# NICLEO-XXXXRX.net
KiCad netlist of a schematic drawn in Altium Designer
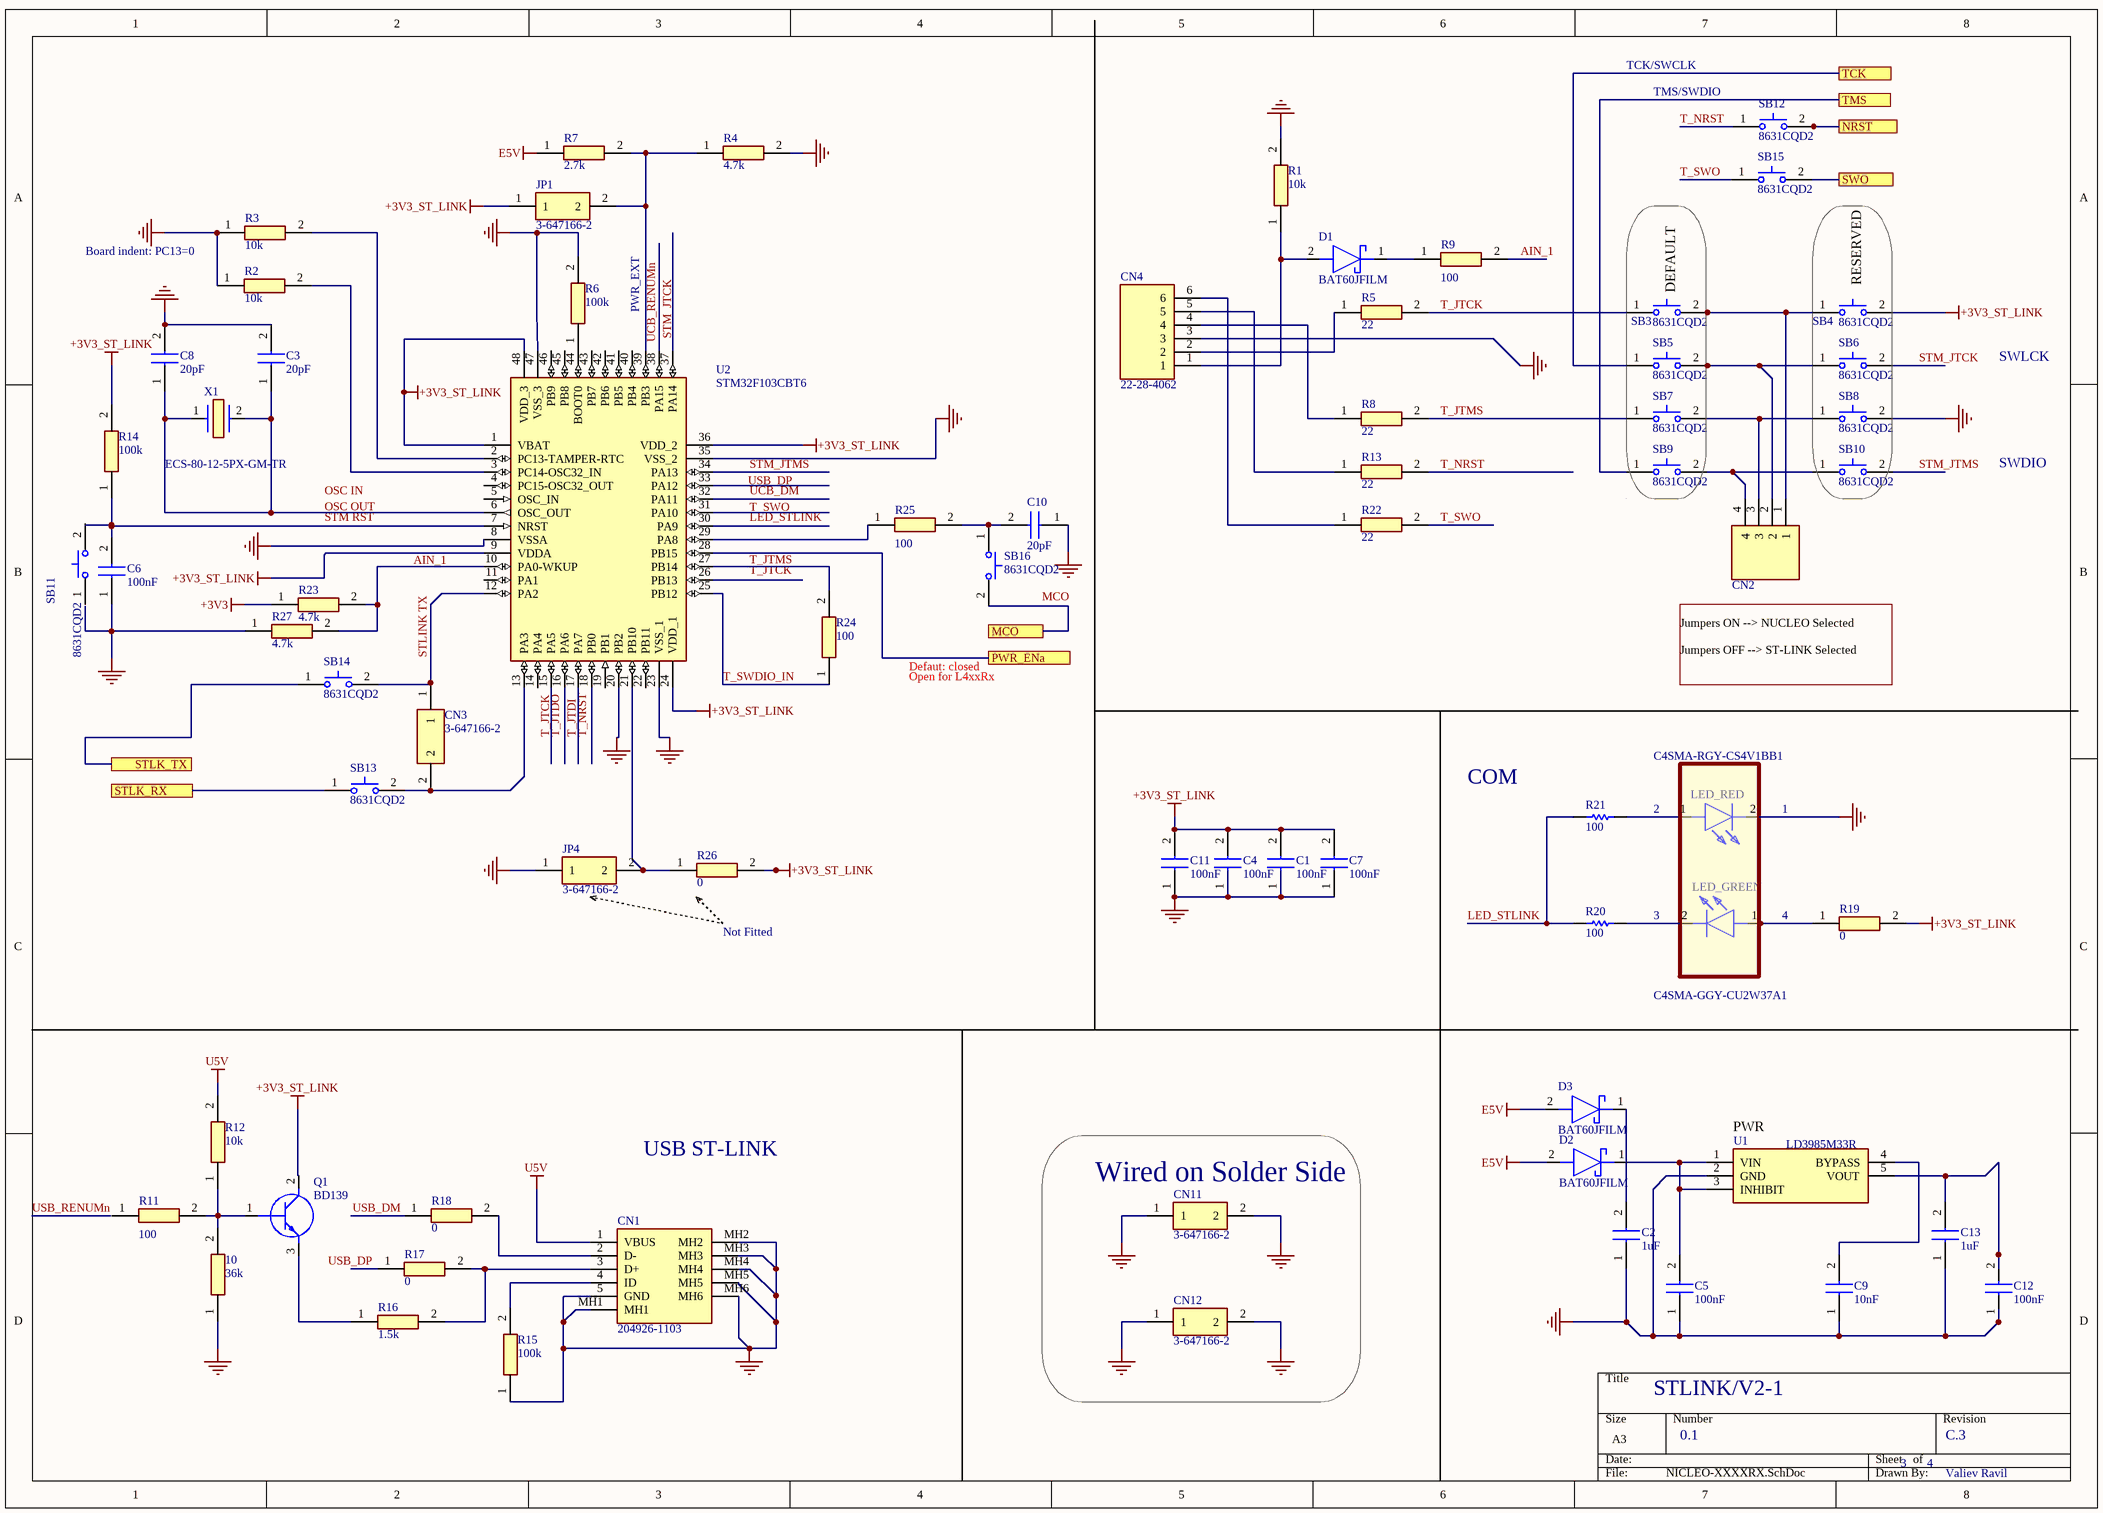
[diagram p0: NICLEO-XXXXRX.SchDoc]

(export (version "E")
  (design (tool "Eeschema 10.0.6"))
  (components
    (comp (ref "10")
      (value "36k")
      (footprint "SamacSys:RESC2012X55N")
      (description "Resistor")
      (fields (field (name "MANUFACTURER_PART_NUMBER") "TNPW080536K0BEEA"))
      (libsource (lib "*") (part "TNPW080536K0BEEA"))
    )
    (comp (ref "C1")
      (value "100nF")
      (footprint "SamacSys:CAPC1608X90N")
      (description "Capacitor")
      (fields
        (field (name "MANUFACTURER_PART_NUMBER") "06035C104K4T4A")
        (field (name "MOUSER PART NUMBER") "581-06035C104K4T4A")
      )
      (libsource (lib "*") (part "06035C104K4T4A"))
    )
    (comp (ref "C2")
      (value "1uF")
      (footprint "SamacSys:MAJx16")
      (description "Capacitor")
      (fields (field (name "MANUFACTURER_PART_NUMBER") "MAJCT168BB7105KTEA01"))
      (libsource (lib "*") (part "MAJCT168BB7105KTEA01"))
    )
    (comp (ref "C3")
      (value "20pF")
      (footprint "SamacSys:C1206")
      (description "Capacitor")
      (fields (field (name "MANUFACTURER_PART_NUMBER") "C1206C200KCGACTU"))
      (libsource (lib "*") (part "C1206C200KCGACTU"))
    )
    (comp (ref "C4")
      (value "100nF")
      (footprint "SamacSys:CAPC1608X90N")
      (description "Capacitor")
      (fields
        (field (name "MANUFACTURER_PART_NUMBER") "06035C104K4T4A")
        (field (name "MOUSER PART NUMBER") "581-06035C104K4T4A")
      )
      (libsource (lib "*") (part "06035C104K4T4A"))
    )
    (comp (ref "C5")
      (value "100nF")
      (footprint "SamacSys:CAPC1608X90N")
      (description "Capacitor")
      (fields
        (field (name "MANUFACTURER_PART_NUMBER") "06035C104K4T4A")
        (field (name "MOUSER PART NUMBER") "581-06035C104K4T4A")
      )
      (libsource (lib "*") (part "06035C104K4T4A"))
    )
    (comp (ref "C6")
      (value "100nF")
      (footprint "SamacSys:CAPC1608X90N")
      (description "Capacitor")
      (fields
        (field (name "MANUFACTURER_PART_NUMBER") "06035C104K4T4A")
        (field (name "MOUSER PART NUMBER") "581-06035C104K4T4A")
      )
      (libsource (lib "*") (part "06035C104K4T4A"))
    )
    (comp (ref "C7")
      (value "100nF")
      (footprint "SamacSys:CAPC1608X90N")
      (description "Capacitor")
      (fields
        (field (name "MANUFACTURER_PART_NUMBER") "06035C104K4T4A")
        (field (name "MOUSER PART NUMBER") "581-06035C104K4T4A")
      )
      (libsource (lib "*") (part "06035C104K4T4A"))
    )
    (comp (ref "C8")
      (value "20pF")
      (footprint "SamacSys:C1206")
      (description "Capacitor")
      (fields (field (name "MANUFACTURER_PART_NUMBER") "C1206C200KCGACTU"))
      (libsource (lib "*") (part "C1206C200KCGACTU"))
    )
    (comp (ref "C9")
      (value "10nF")
      (footprint "SamacSys:CAPC3316X145N")
      (description "Capacitor")
      (fields
        (field (name "MANUFACTURER_PART_NUMBER") "KGM31GCG2J103JU")
        (field (name "MOUSER PART NUMBER") "581-KGM31GCG2J103JU")
      )
      (libsource (lib "*") (part "KGM31GCG2J103JU"))
    )
    (comp (ref "C10")
      (value "20pF")
      (footprint "SamacSys:C1206")
      (description "Capacitor")
      (fields (field (name "MANUFACTURER_PART_NUMBER") "C1206C200KCGACTU"))
      (libsource (lib "*") (part "C1206C200KCGACTU"))
    )
    (comp (ref "C11")
      (value "100nF")
      (footprint "SamacSys:CAPC1608X90N")
      (description "Capacitor")
      (fields
        (field (name "MANUFACTURER_PART_NUMBER") "06035C104K4T4A")
        (field (name "MOUSER PART NUMBER") "581-06035C104K4T4A")
      )
      (libsource (lib "*") (part "06035C104K4T4A"))
    )
    (comp (ref "C12")
      (value "100nF")
      (footprint "SamacSys:CAPC1608X90N")
      (description "Capacitor")
      (fields
        (field (name "MANUFACTURER_PART_NUMBER") "06035C104K4T4A")
        (field (name "MOUSER PART NUMBER") "581-06035C104K4T4A")
      )
      (libsource (lib "*") (part "06035C104K4T4A"))
    )
    (comp (ref "C13")
      (value "1uF")
      (footprint "SamacSys:MAJx16")
      (description "Capacitor")
      (fields (field (name "MANUFACTURER_PART_NUMBER") "MAJCT168BB7105KTEA01"))
      (libsource (lib "*") (part "MAJCT168BB7105KTEA01"))
    )
    (comp (ref "CN1")
      (value "204926-1103")
      (footprint "SamacSys:2049261103")
      (description "Connector")
      (fields (field (name "MOUSER PART NUMBER") "538-204926-1103"))
      (libsource (lib "*") (part "204926-1103"))
    )
    (comp (ref "CN2")
      (value "53014-0410")
      (footprint "SamacSys:SHDR4W60P0X200_1X4_1200X435X1000P")
      (description "Connector")
      (fields (field (name "MOUSER PART NUMBER") "538-53014-0410"))
      (libsource (lib "*") (part "53014-0410"))
    )
    (comp (ref "CN3")
      (value "3-647166-2")
      (footprint "SamacSys:36471662")
      (description "Connector")
      (fields (field (name "MOUSER PART NUMBER") "571-3-647166-2"))
      (libsource (lib "") (part "3-647166-2_1"))
    )
    (comp (ref "CN4")
      (value "22-28-4062")
      (footprint "SamacSys:HDRV6W66P0X254_1X6_1524X249X838P")
      (description "Connector")
      (fields (field (name "MOUSER PART NUMBER") "538-22-28-4062"))
      (libsource (lib "*") (part "22-28-4062"))
    )
    (comp (ref "CN11")
      (value "3-647166-2")
      (footprint "SamacSys:36471662")
      (description "Connector")
      (fields (field (name "MOUSER PART NUMBER") "571-3-647166-2"))
      (libsource (lib "*") (part "3-647166-2"))
    )
    (comp (ref "CN12")
      (value "3-647166-2")
      (footprint "SamacSys:36471662")
      (description "Connector")
      (fields (field (name "MOUSER PART NUMBER") "571-3-647166-2"))
      (libsource (lib "*") (part "3-647166-2"))
    )
    (comp (ref "D1")
      (value "BAT60JFILM")
      (footprint "SamacSys:SOD2513X117N")
      (description "Schottky Diode")
      (fields (field (name "MOUSER PART NUMBER") "511-BAT60JFILM"))
      (libsource (lib "*") (part "BAT60JFILM"))
    )
    (comp (ref "D2")
      (value "BAT60JFILM")
      (footprint "SamacSys:SOD2513X117N")
      (description "Schottky Diode")
      (fields (field (name "MOUSER PART NUMBER") "511-BAT60JFILM"))
      (libsource (lib "*") (part "BAT60JFILM"))
    )
    (comp (ref "D3")
      (value "BAT60JFILM")
      (footprint "SamacSys:SOD2513X117N")
      (description "Schottky Diode")
      (fields (field (name "MOUSER PART NUMBER") "511-BAT60JFILM"))
      (libsource (lib "*") (part "BAT60JFILM"))
    )
    (comp (ref "JP1")
      (value "3-647166-2")
      (footprint "SamacSys:36471662")
      (description "Connector")
      (fields (field (name "MOUSER PART NUMBER") "571-3-647166-2"))
      (libsource (lib "*") (part "3-647166-2"))
    )
    (comp (ref "JP4")
      (value "3-647166-2")
      (footprint "SamacSys:36471662")
      (description "Connector")
      (fields (field (name "MOUSER PART NUMBER") "571-3-647166-2"))
      (libsource (lib "*") (part "3-647166-2"))
    )
    (comp (ref "LED_GREEN")
      (value "C4SMA-GGY-CU2W37A1")
      (footprint "SamacSys:C4SMAGGYCU2W37A1")
      (description "LED")
      (fields (field (name "MOUSER PART NUMBER") "941-C4SMAGGYCU2W37A1"))
      (libsource (lib "*") (part "C4SMA-GGY-CU2W37A1"))
    )
    (comp (ref "LED_RED")
      (value "C4SMA-RGY-CS4V1BB1")
      (footprint "SamacSys:C4SMARGYCS4V1BB1")
      (description "LED")
      (fields (field (name "MOUSER PART NUMBER") "941-C4SMARGYCS4V1BB1"))
      (libsource (lib "*") (part "C4SMA-RGY-CS4V1BB1"))
    )
    (comp (ref "Q1")
      (value "BD139")
      (footprint "SamacSys:TO254P290X760X1320-3P")
      (description "Transistor BJT NPN")
      (fields (field (name "MOUSER PART NUMBER") "511-BD139"))
      (libsource (lib "*") (part "BD139"))
    )
    (comp (ref "R1")
      (value "10k")
      (footprint "SamacSys:RESC3216X74N")
      (description "Resistor")
      (fields
        (field (name "MANUFACTURER_PART_NUMBER") "CRMV1206AF10K0FKE5")
        (field (name "MOUSER PART NUMBER") "71-RMV1206AF10K0FKE5")
      )
      (libsource (lib "*") (part "CRMV1206AF10K0FKE5"))
    )
    (comp (ref "R2")
      (value "10k")
      (footprint "SamacSys:RESC3216X74N")
      (description "Resistor")
      (fields
        (field (name "MANUFACTURER_PART_NUMBER") "CRMV1206AF10K0FKE5")
        (field (name "MOUSER PART NUMBER") "71-RMV1206AF10K0FKE5")
      )
      (libsource (lib "") (part "CRMV1206AF10K0FKE5_1"))
    )
    (comp (ref "R3")
      (value "10k")
      (footprint "SamacSys:RESC3216X74N")
      (description "Resistor")
      (fields
        (field (name "MANUFACTURER_PART_NUMBER") "CRMV1206AF10K0FKE5")
        (field (name "MOUSER PART NUMBER") "71-RMV1206AF10K0FKE5")
      )
      (libsource (lib "") (part "CRMV1206AF10K0FKE5_1"))
    )
    (comp (ref "R4")
      (value "4.7k")
      (footprint "SamacSys:RESC1005X37N")
      (description "Resistor")
      (fields
        (field (name "MANUFACTURER_PART_NUMBER") "MCS04020D4701BE000")
        (field (name "MOUSER PART NUMBER") "594-MCS04020D4701BE0")
      )
      (libsource (lib "*") (part "MCS04020D4701BE000"))
    )
    (comp (ref "R5")
      (value "22")
      (footprint "SamacSys:ERA6AEB1020V")
      (description "Resistor")
      (fields
        (field (name "MANUFACTURER_PART_NUMBER") "ERA-6AHD220V")
        (field (name "MOUSER PART NUMBER") "667-ERA-6AHD220V")
      )
      (libsource (lib "*") (part "ERA-6AHD220V"))
    )
    (comp (ref "R6")
      (value "100k")
      (footprint "SamacSys:RESC1005X40N")
      (description "Resistor")
      (fields
        (field (name "MANUFACTURER_PART_NUMBER") "SFR01MZPF1003")
        (field (name "MOUSER PART NUMBER") "755-SFR01MZPF1003")
      )
      (libsource (lib "*") (part "SFR01MZPF1003"))
    )
    (comp (ref "R7")
      (value "2.7k")
      (footprint "SamacSys:RESC3225X70N")
      (description "Resistor")
      (fields
        (field (name "MANUFACTURER_PART_NUMBER") "CRCW12102K70FKEAHP")
        (field (name "MOUSER PART NUMBER") "71-CRCW12102K70FKEAH")
      )
      (libsource (lib "*") (part "CRCW12102K70FKEAHP"))
    )
    (comp (ref "R8")
      (value "22")
      (footprint "SamacSys:ERA6AEB1020V")
      (description "Resistor")
      (fields
        (field (name "MANUFACTURER_PART_NUMBER") "ERA-6AHD220V")
        (field (name "MOUSER PART NUMBER") "667-ERA-6AHD220V")
      )
      (libsource (lib "*") (part "ERA-6AHD220V"))
    )
    (comp (ref "R9")
      (value "100")
      (footprint "SamacSys:ERA3AEB101V")
      (description "Resistor")
      (fields
        (field (name "MANUFACTURER_PART_NUMBER") "ERA-3AED101V")
        (field (name "MOUSER PART NUMBER") "667-ERA-3AED101V")
      )
      (libsource (lib "*") (part "ERA-3AED101V"))
    )
    (comp (ref "R11")
      (value "100")
      (footprint "SamacSys:ERA3AEB101V")
      (description "Resistor")
      (fields
        (field (name "MANUFACTURER_PART_NUMBER") "ERA-3AED101V")
        (field (name "MOUSER PART NUMBER") "667-ERA-3AED101V")
      )
      (libsource (lib "*") (part "ERA-3AED101V"))
    )
    (comp (ref "R12")
      (value "10k")
      (footprint "SamacSys:RESC3216X74N")
      (description "Resistor")
      (fields
        (field (name "MANUFACTURER_PART_NUMBER") "CRMV1206AF10K0FKE5")
        (field (name "MOUSER PART NUMBER") "71-RMV1206AF10K0FKE5")
      )
      (libsource (lib "*") (part "CRMV1206AF10K0FKE5"))
    )
    (comp (ref "R13")
      (value "22")
      (footprint "SamacSys:ERA6AEB1020V")
      (description "Resistor")
      (fields
        (field (name "MANUFACTURER_PART_NUMBER") "ERA-6AHD220V")
        (field (name "MOUSER PART NUMBER") "667-ERA-6AHD220V")
      )
      (libsource (lib "*") (part "ERA-6AHD220V"))
    )
    (comp (ref "R14")
      (value "100k")
      (footprint "SamacSys:RESC1005X40N")
      (description "Resistor")
      (fields
        (field (name "MANUFACTURER_PART_NUMBER") "SFR01MZPF1003")
        (field (name "MOUSER PART NUMBER") "755-SFR01MZPF1003")
      )
      (libsource (lib "*") (part "SFR01MZPF1003"))
    )
    (comp (ref "R15")
      (value "100k")
      (footprint "SamacSys:RESC1005X40N")
      (description "Resistor")
      (fields
        (field (name "MANUFACTURER_PART_NUMBER") "SFR01MZPF1003")
        (field (name "MOUSER PART NUMBER") "755-SFR01MZPF1003")
      )
      (libsource (lib "*") (part "SFR01MZPF1003"))
    )
    (comp (ref "R16")
      (value "1.5k")
      (footprint "SamacSys:RESC3116X65N")
      (description "Resistor")
      (fields
        (field (name "MANUFACTURER_PART_NUMBER") "CRCW12061K50FKEAHP")
        (field (name "MOUSER PART NUMBER") "71-CRCW12061K50FKEAH")
      )
      (libsource (lib "*") (part "CRCW12061K50FKEAHP"))
    )
    (comp (ref "R17")
      (value "0")
      (footprint "SamacSys:RESC2013X84N")
      (description "Resistor")
      (fields
        (field (name "MANUFACTURER_PART_NUMBER") "WSL080500000ZEA9")
        (field (name "MOUSER PART NUMBER") "71-WSL080500000ZEA9")
      )
      (libsource (lib "*") (part "WSL080500000ZEA9"))
    )
    (comp (ref "R18")
      (value "0")
      (footprint "SamacSys:RESC2013X84N")
      (description "Resistor")
      (fields
        (field (name "MANUFACTURER_PART_NUMBER") "WSL080500000ZEA9")
        (field (name "MOUSER PART NUMBER") "71-WSL080500000ZEA9")
      )
      (libsource (lib "*") (part "WSL080500000ZEA9"))
    )
    (comp (ref "R19")
      (value "0")
      (footprint "SamacSys:RESC2013X84N")
      (description "Resistor")
      (fields
        (field (name "MANUFACTURER_PART_NUMBER") "WSL080500000ZEA9")
        (field (name "MOUSER PART NUMBER") "71-WSL080500000ZEA9")
      )
      (libsource (lib "*") (part "WSL080500000ZEA9"))
    )
    (comp (ref "R20")
      (value "100")
      (description "Resistor")
      (libsource (lib "Simulation Generic Components") (part "Resistor"))
    )
    (comp (ref "R21")
      (value "100")
      (description "Resistor")
      (libsource (lib "Simulation Generic Components") (part "Resistor"))
    )
    (comp (ref "R22")
      (value "22")
      (footprint "SamacSys:ERA6AEB1020V")
      (description "Resistor")
      (fields
        (field (name "MANUFACTURER_PART_NUMBER") "ERA-6AHD220V")
        (field (name "MOUSER PART NUMBER") "667-ERA-6AHD220V")
      )
      (libsource (lib "*") (part "ERA-6AHD220V"))
    )
    (comp (ref "R23")
      (value "4.7k")
      (footprint "SamacSys:RESC1005X37N")
      (description "Resistor")
      (fields
        (field (name "MANUFACTURER_PART_NUMBER") "MCS04020D4701BE000")
        (field (name "MOUSER PART NUMBER") "594-MCS04020D4701BE0")
      )
      (libsource (lib "*") (part "MCS04020D4701BE000"))
    )
    (comp (ref "R24")
      (value "100")
      (footprint "SamacSys:ERA3AEB101V")
      (description "Resistor")
      (fields
        (field (name "MANUFACTURER_PART_NUMBER") "ERA-3AED101V")
        (field (name "MOUSER PART NUMBER") "667-ERA-3AED101V")
      )
      (libsource (lib "") (part "ERA-3AED101V_1"))
    )
    (comp (ref "R25")
      (value "100")
      (footprint "SamacSys:ERA3AEB101V")
      (description "Resistor")
      (fields
        (field (name "MANUFACTURER_PART_NUMBER") "ERA-3AED101V")
        (field (name "MOUSER PART NUMBER") "667-ERA-3AED101V")
      )
      (libsource (lib "*") (part "ERA-3AED101V"))
    )
    (comp (ref "R26")
      (value "0")
      (footprint "SamacSys:RESC2013X84N")
      (description "Resistor")
      (fields
        (field (name "MANUFACTURER_PART_NUMBER") "WSL080500000ZEA9")
        (field (name "MOUSER PART NUMBER") "71-WSL080500000ZEA9")
      )
      (libsource (lib "*") (part "WSL080500000ZEA9"))
    )
    (comp (ref "R27")
      (value "4.7k")
      (footprint "SamacSys:RESC1005X37N")
      (description "Resistor")
      (fields
        (field (name "MANUFACTURER_PART_NUMBER") "MCS04020D4701BE000")
        (field (name "MOUSER PART NUMBER") "594-MCS04020D4701BE0")
      )
      (libsource (lib "*") (part "MCS04020D4701BE000"))
    )
    (comp (ref "SB3")
      (value "8631CQD2")
      (footprint "SamacSys:8631CQD2")
      (description "Switch (2-Pin Push)")
      (fields (field (name "MOUSER PART NUMBER") "611-8631-261"))
      (libsource (lib "*") (part "8631CQD2"))
    )
    (comp (ref "SB4")
      (value "8631CQD2")
      (footprint "SamacSys:8631CQD2")
      (description "Switch (2-Pin Push)")
      (fields (field (name "MOUSER PART NUMBER") "611-8631-261"))
      (libsource (lib "*") (part "8631CQD2"))
    )
    (comp (ref "SB5")
      (value "8631CQD2")
      (footprint "SamacSys:8631CQD2")
      (description "Switch (2-Pin Push)")
      (fields (field (name "MOUSER PART NUMBER") "611-8631-261"))
      (libsource (lib "*") (part "8631CQD2"))
    )
    (comp (ref "SB6")
      (value "8631CQD2")
      (footprint "SamacSys:8631CQD2")
      (description "Switch (2-Pin Push)")
      (fields (field (name "MOUSER PART NUMBER") "611-8631-261"))
      (libsource (lib "*") (part "8631CQD2"))
    )
    (comp (ref "SB7")
      (value "8631CQD2")
      (footprint "SamacSys:8631CQD2")
      (description "Switch (2-Pin Push)")
      (fields (field (name "MOUSER PART NUMBER") "611-8631-261"))
      (libsource (lib "*") (part "8631CQD2"))
    )
    (comp (ref "SB8")
      (value "8631CQD2")
      (footprint "SamacSys:8631CQD2")
      (description "Switch (2-Pin Push)")
      (fields (field (name "MOUSER PART NUMBER") "611-8631-261"))
      (libsource (lib "*") (part "8631CQD2"))
    )
    (comp (ref "SB9")
      (value "8631CQD2")
      (footprint "SamacSys:8631CQD2")
      (description "Switch (2-Pin Push)")
      (fields (field (name "MOUSER PART NUMBER") "611-8631-261"))
      (libsource (lib "*") (part "8631CQD2"))
    )
    (comp (ref "SB10")
      (value "8631CQD2")
      (footprint "SamacSys:8631CQD2")
      (description "Switch (2-Pin Push)")
      (fields (field (name "MOUSER PART NUMBER") "611-8631-261"))
      (libsource (lib "*") (part "8631CQD2"))
    )
    (comp (ref "SB11")
      (value "8631CQD2")
      (footprint "SamacSys:8631CQD2")
      (description "Switch (2-Pin Push)")
      (fields (field (name "MOUSER PART NUMBER") "611-8631-261"))
      (libsource (lib "*") (part "8631CQD2"))
    )
    (comp (ref "SB12")
      (value "8631CQD2")
      (footprint "SamacSys:8631CQD2")
      (description "Switch (2-Pin Push)")
      (fields (field (name "MOUSER PART NUMBER") "611-8631-261"))
      (libsource (lib "*") (part "8631CQD2"))
    )
    (comp (ref "SB13")
      (value "8631CQD2")
      (footprint "SamacSys:8631CQD2")
      (description "Switch (2-Pin Push)")
      (fields (field (name "MOUSER PART NUMBER") "611-8631-261"))
      (libsource (lib "*") (part "8631CQD2"))
    )
    (comp (ref "SB14")
      (value "8631CQD2")
      (footprint "SamacSys:8631CQD2")
      (description "Switch (2-Pin Push)")
      (fields (field (name "MOUSER PART NUMBER") "611-8631-261"))
      (libsource (lib "*") (part "8631CQD2"))
    )
    (comp (ref "SB15")
      (value "8631CQD2")
      (footprint "SamacSys:8631CQD2")
      (description "Switch (2-Pin Push)")
      (fields (field (name "MOUSER PART NUMBER") "611-8631-261"))
      (libsource (lib "*") (part "8631CQD2"))
    )
    (comp (ref "SB16")
      (value "8631CQD2")
      (footprint "SamacSys:8631CQD2")
      (description "Switch (2-Pin Push)")
      (fields (field (name "MOUSER PART NUMBER") "611-8631-261"))
      (libsource (lib "*") (part "8631CQD2"))
    )
    (comp (ref "U1")
      (value "LD3985M33R")
      (footprint "SamacSys:SOT95P280X145-5N")
      (description "Integrated Circuit")
      (fields (field (name "MOUSER PART NUMBER") "511-LD3985M33R"))
      (libsource (lib "*") (part "LD3985M33R"))
    )
    (comp (ref "U2")
      (value "STM32F103CBT6")
      (footprint "SamacSys:QFP50P900X900X160-48N")
      (description "Integrated Circuit")
      (fields (field (name "MOUSER PART NUMBER") "511-STM32F103CBT6"))
      (libsource (lib "*") (part "STM32F103CBT6"))
    )
    (comp (ref "X1")
      (value "ECS-80-12-5PX-GM-TR")
      (footprint "SamacSys:ECS80125PXGMTR")
      (description "Crystal or Oscillator")
      (fields (field (name "MOUSER PART NUMBER") "520-80-12-5PX-GM-TR"))
      (libsource (lib "*") (part "ECS-80-12-5PX-GM-TR"))
    )
  )
  (nets
    (net (code "1") (name "+3V3") (class "Default")
      (node (ref "R23") (pin "1") (pinfunction "1_1") (pintype "passive"))
    )
    (net (code "2") (name "+3V3_ST_LINK") (class "Default")
      (node (ref "C1") (pin "2") (pinfunction "2_2") (pintype "passive"))
      (node (ref "C11") (pin "2") (pinfunction "2_2") (pintype "passive"))
      (node (ref "C4") (pin "2") (pinfunction "2_2") (pintype "passive"))
      (node (ref "C7") (pin "2") (pinfunction "2_2") (pintype "passive"))
      (node (ref "JP1") (pin "1") (pinfunction "1_1") (pintype "passive"))
      (node (ref "Q1") (pin "2") (pinfunction "C_2") (pintype "passive"))
      (node (ref "R14") (pin "2") (pinfunction "2_2") (pintype "passive"))
      (node (ref "R19") (pin "2") (pinfunction "2_2") (pintype "passive"))
      (node (ref "R26") (pin "2") (pinfunction "2_2") (pintype "passive"))
      (node (ref "SB4") (pin "2") (pinfunction "N.O._2_2") (pintype "passive"))
      (node (ref "U2") (pin "1") (pinfunction "VBAT_1") (pintype "passive"))
      (node (ref "U2") (pin "24") (pinfunction "VDD_1_24") (pintype "passive"))
      (node (ref "U2") (pin "36") (pinfunction "VDD_2_36") (pintype "passive"))
      (node (ref "U2") (pin "48") (pinfunction "VDD_3_48") (pintype "passive"))
      (node (ref "U2") (pin "9") (pinfunction "VDDA_9") (pintype "passive"))
    )
    (net (code "3") (name "/MCO") (class "Default")
      (node (ref "SB16") (pin "2") (pinfunction "N.O._2_2") (pintype "passive"))
    )
    (net (code "4") (name "/NRST") (class "Default")
      (node (ref "SB12") (pin "2") (pinfunction "N.O._2_2") (pintype "passive"))
    )
    (net (code "5") (name "/PWR_ENa") (class "Default")
      (node (ref "U2") (pin "28") (pinfunction "PB15_28") (pintype "bidirectional"))
    )
    (net (code "6") (name "/STLK_RX") (class "Default")
      (node (ref "SB13") (pin "1") (pinfunction "N.O._1_1") (pintype "passive"))
    )
    (net (code "7") (name "/STLK_TX") (class "Default")
      (node (ref "SB14") (pin "1") (pinfunction "N.O._1_1") (pintype "passive"))
    )
    (net (code "8") (name "/SWO") (class "Default")
      (node (ref "SB15") (pin "2") (pinfunction "N.O._2_2") (pintype "passive"))
    )
    (net (code "9") (name "/TCK") (class "Default")
      (node (ref "SB5") (pin "1") (pinfunction "N.O._1_1") (pintype "passive"))
    )
    (net (code "10") (name "/TMS") (class "Default")
      (node (ref "SB9") (pin "1") (pinfunction "N.O._1_1") (pintype "passive"))
    )
    (net (code "11") (name "E5V") (class "Default")
      (node (ref "D2") (pin "2") (pinfunction "A_2") (pintype "passive"))
      (node (ref "D3") (pin "2") (pinfunction "A_2") (pintype "passive"))
      (node (ref "R7") (pin "1") (pinfunction "1_1") (pintype "passive"))
    )
    (net (code "12") (name "GND") (class "Default")
      (node (ref "10") (pin "1") (pinfunction "1_1") (pintype "passive"))
      (node (ref "C1") (pin "1") (pinfunction "1_1") (pintype "passive"))
      (node (ref "C10") (pin "1") (pinfunction "1_1") (pintype "passive"))
      (node (ref "C11") (pin "1") (pinfunction "1_1") (pintype "passive"))
      (node (ref "C12") (pin "1") (pinfunction "1_1") (pintype "passive"))
      (node (ref "C13") (pin "1") (pinfunction "1_1") (pintype "passive"))
      (node (ref "C2") (pin "1") (pinfunction "1_1") (pintype "passive"))
      (node (ref "C3") (pin "2") (pinfunction "2_2") (pintype "passive"))
      (node (ref "C4") (pin "1") (pinfunction "1_1") (pintype "passive"))
      (node (ref "C5") (pin "1") (pinfunction "1_1") (pintype "passive"))
      (node (ref "C6") (pin "1") (pinfunction "1_1") (pintype "passive"))
      (node (ref "C7") (pin "1") (pinfunction "1_1") (pintype "passive"))
      (node (ref "C8") (pin "2") (pinfunction "2_2") (pintype "passive"))
      (node (ref "C9") (pin "1") (pinfunction "1_1") (pintype "passive"))
      (node (ref "CN1") (pin "5") (pinfunction "GND_5") (pintype "passive"))
      (node (ref "CN1") (pin "MH1") (pinfunction "MH1_MH1") (pintype "passive"))
      (node (ref "CN1") (pin "MH2") (pinfunction "MH2_MH2") (pintype "passive"))
      (node (ref "CN1") (pin "MH3") (pinfunction "MH3_MH3") (pintype "passive"))
      (node (ref "CN1") (pin "MH4") (pinfunction "MH4_MH4") (pintype "passive"))
      (node (ref "CN1") (pin "MH5") (pinfunction "MH5_MH5") (pintype "passive"))
      (node (ref "CN1") (pin "MH6") (pinfunction "MH6_MH6") (pintype "passive"))
      (node (ref "CN11") (pin "1") (pinfunction "1_1") (pintype "passive"))
      (node (ref "CN11") (pin "2") (pinfunction "2_2") (pintype "passive"))
      (node (ref "CN12") (pin "1") (pinfunction "1_1") (pintype "passive"))
      (node (ref "CN12") (pin "2") (pinfunction "2_2") (pintype "passive"))
      (node (ref "CN4") (pin "3") (pinfunction "3_3") (pintype "passive"))
      (node (ref "JP4") (pin "1") (pinfunction "1_1") (pintype "passive"))
      (node (ref "LED_RED") (pin "2") (pinfunction "K_2") (pintype "passive"))
      (node (ref "R1") (pin "2") (pinfunction "2_2") (pintype "passive"))
      (node (ref "R15") (pin "1") (pinfunction "1_1") (pintype "passive"))
      (node (ref "R2") (pin "1") (pinfunction "1_1") (pintype "passive"))
      (node (ref "R27") (pin "1") (pinfunction "1_1") (pintype "passive"))
      (node (ref "R3") (pin "1") (pinfunction "1_1") (pintype "passive"))
      (node (ref "R4") (pin "2") (pinfunction "2_2") (pintype "passive"))
      (node (ref "R6") (pin "2") (pinfunction "2_2") (pintype "passive"))
      (node (ref "SB8") (pin "2") (pinfunction "N.O._2_2") (pintype "passive"))
      (node (ref "U1") (pin "2") (pinfunction "GND_2") (pintype "passive"))
      (node (ref "U2") (pin "20") (pinfunction "PB2_20") (pintype "bidirectional"))
      (node (ref "U2") (pin "23") (pinfunction "VSS_1_23") (pintype "passive"))
      (node (ref "U2") (pin "35") (pinfunction "VSS_2_35") (pintype "passive"))
      (node (ref "U2") (pin "47") (pinfunction "VSS_3_47") (pintype "passive"))
      (node (ref "U2") (pin "8") (pinfunction "VSSA_8") (pintype "passive"))
    )
    (net (code "13") (name "Net-(CN1-D+)") (class "Default")
      (node (ref "CN1") (pin "3") (pinfunction "D+_3") (pintype "passive"))
      (node (ref "R16") (pin "2") (pinfunction "2_2") (pintype "passive"))
      (node (ref "R17") (pin "2") (pinfunction "2_2") (pintype "passive"))
    )
    (net (code "14") (name "Net-(CN1-D-)") (class "Default")
      (node (ref "CN1") (pin "2") (pinfunction "D-_2") (pintype "passive"))
      (node (ref "R18") (pin "2") (pinfunction "2_2") (pintype "passive"))
    )
    (net (code "15") (name "Net-(CN1-ID)") (class "Default")
      (node (ref "CN1") (pin "4") (pinfunction "ID_4") (pintype "passive"))
      (node (ref "R15") (pin "2") (pinfunction "2_2") (pintype "passive"))
    )
    (net (code "16") (name "Net-(CN4-Pad2)") (class "Default")
      (node (ref "CN4") (pin "2") (pinfunction "2_2") (pintype "passive"))
      (node (ref "R5") (pin "1") (pinfunction "1_1") (pintype "passive"))
    )
    (net (code "17") (name "Net-(CN4-Pad4)") (class "Default")
      (node (ref "CN4") (pin "4") (pinfunction "4_4") (pintype "passive"))
      (node (ref "R8") (pin "1") (pinfunction "1_1") (pintype "passive"))
    )
    (net (code "18") (name "Net-(CN4-Pad5)") (class "Default")
      (node (ref "CN4") (pin "5") (pinfunction "5_5") (pintype "passive"))
      (node (ref "R13") (pin "1") (pinfunction "1_1") (pintype "passive"))
    )
    (net (code "19") (name "Net-(CN4-Pad6)") (class "Default")
      (node (ref "CN4") (pin "6") (pinfunction "6_6") (pintype "passive"))
      (node (ref "R22") (pin "1") (pinfunction "1_1") (pintype "passive"))
    )
    (net (code "20") (name "Net-(D1-A)") (class "Default")
      (node (ref "CN4") (pin "1") (pinfunction "1_1") (pintype "passive"))
      (node (ref "D1") (pin "2") (pinfunction "A_2") (pintype "passive"))
      (node (ref "R1") (pin "1") (pinfunction "1_1") (pintype "passive"))
    )
    (net (code "21") (name "Net-(D1-K)") (class "Default")
      (node (ref "D1") (pin "1") (pinfunction "K_1") (pintype "passive"))
      (node (ref "R9") (pin "1") (pinfunction "1_1") (pintype "passive"))
    )
    (net (code "22") (name "Net-(D2-K)") (class "Default")
      (node (ref "C5") (pin "2") (pinfunction "2_2") (pintype "passive"))
      (node (ref "D2") (pin "1") (pinfunction "K_1") (pintype "passive"))
      (node (ref "U1") (pin "1") (pinfunction "VIN_1") (pintype "passive"))
      (node (ref "U1") (pin "3") (pinfunction "INHIBIT_3") (pintype "passive"))
    )
    (net (code "23") (name "Net-(D3-K)") (class "Default")
      (node (ref "C2") (pin "2") (pinfunction "2_2") (pintype "passive"))
      (node (ref "D3") (pin "1") (pinfunction "K_1") (pintype "passive"))
    )
    (net (code "24") (name "Net-(LED_GREEN-A)") (class "Default")
      (node (ref "LED_GREEN") (pin "1") (pinfunction "A_1") (pintype "passive"))
      (node (ref "R19") (pin "1") (pinfunction "1_1") (pintype "passive"))
    )
    (net (code "25") (name "Net-(LED_GREEN-K)") (class "Default")
      (node (ref "LED_GREEN") (pin "2") (pinfunction "K_2") (pintype "passive"))
      (node (ref "R20") (pin "2") (pinfunction "2_2") (pintype "passive"))
    )
    (net (code "26") (name "Net-(LED_RED-A)") (class "Default")
      (node (ref "LED_RED") (pin "1") (pinfunction "A_1") (pintype "passive"))
      (node (ref "R21") (pin "2") (pinfunction "2_2") (pintype "passive"))
    )
    (net (code "27") (name "Net-(Q1-B)") (class "Default")
      (node (ref "10") (pin "2") (pinfunction "2_2") (pintype "passive"))
      (node (ref "Q1") (pin "1") (pinfunction "B_1") (pintype "passive"))
      (node (ref "R11") (pin "2") (pinfunction "2_2") (pintype "passive"))
      (node (ref "R12") (pin "1") (pinfunction "1_1") (pintype "passive"))
    )
    (net (code "28") (name "Net-(Q1-E)") (class "Default")
      (node (ref "Q1") (pin "3") (pinfunction "E_3") (pintype "passive"))
      (node (ref "R16") (pin "1") (pinfunction "1_1") (pintype "passive"))
    )
    (net (code "29") (name "Net-(R20-Pad1)") (class "Default")
      (node (ref "R20") (pin "1") (pinfunction "1_1") (pintype "passive"))
      (node (ref "R21") (pin "1") (pinfunction "1_1") (pintype "passive"))
    )
    (net (code "30") (name "Net-(SB3-N.O._1)") (class "Default")
      (node (ref "R5") (pin "2") (pinfunction "2_2") (pintype "passive"))
      (node (ref "SB3") (pin "1") (pinfunction "N.O._1_1") (pintype "passive"))
    )
    (net (code "31") (name "Net-(SB3-N.O._2)") (class "Default")
      (node (ref "CN2") (pin "1") (pinfunction "1_1") (pintype "passive"))
      (node (ref "SB3") (pin "2") (pinfunction "N.O._2_2") (pintype "passive"))
      (node (ref "SB4") (pin "1") (pinfunction "N.O._1_1") (pintype "passive"))
    )
    (net (code "32") (name "Net-(SB5-N.O._2)") (class "Default")
      (node (ref "CN2") (pin "2") (pinfunction "2_2") (pintype "passive"))
      (node (ref "SB5") (pin "2") (pinfunction "N.O._2_2") (pintype "passive"))
      (node (ref "SB6") (pin "1") (pinfunction "N.O._1_1") (pintype "passive"))
    )
    (net (code "33") (name "Net-(SB7-N.O._1)") (class "Default")
      (node (ref "R8") (pin "2") (pinfunction "2_2") (pintype "passive"))
      (node (ref "SB7") (pin "1") (pinfunction "N.O._1_1") (pintype "passive"))
    )
    (net (code "34") (name "Net-(SB7-N.O._2)") (class "Default")
      (node (ref "CN2") (pin "3") (pinfunction "3_3") (pintype "passive"))
      (node (ref "SB7") (pin "2") (pinfunction "N.O._2_2") (pintype "passive"))
      (node (ref "SB8") (pin "1") (pinfunction "N.O._1_1") (pintype "passive"))
    )
    (net (code "35") (name "Net-(SB10-N.O._1)") (class "Default")
      (node (ref "CN2") (pin "4") (pinfunction "4_4") (pintype "passive"))
      (node (ref "SB10") (pin "1") (pinfunction "N.O._1_1") (pintype "passive"))
      (node (ref "SB9") (pin "2") (pinfunction "N.O._2_2") (pintype "passive"))
    )
    (net (code "36") (name "Net-(SB13-N.O._2)") (class "Default")
      (node (ref "CN3") (pin "2") (pinfunction "2_2") (pintype "passive"))
      (node (ref "SB13") (pin "2") (pinfunction "N.O._2_2") (pintype "passive"))
      (node (ref "U2") (pin "13") (pinfunction "PA3_13") (pintype "bidirectional"))
    )
    (net (code "37") (name "Net-(SB14-N.O._2)") (class "Default")
      (node (ref "CN3") (pin "1") (pinfunction "1_1") (pintype "passive"))
      (node (ref "SB14") (pin "2") (pinfunction "N.O._2_2") (pintype "passive"))
      (node (ref "U2") (pin "12") (pinfunction "PA2_12") (pintype "bidirectional"))
    )
    (net (code "38") (name "Net-(SB16-N.O._1)") (class "Default")
      (node (ref "C10") (pin "2") (pinfunction "2_2") (pintype "passive"))
      (node (ref "R25") (pin "2") (pinfunction "2_2") (pintype "passive"))
      (node (ref "SB16") (pin "1") (pinfunction "N.O._1_1") (pintype "passive"))
    )
    (net (code "39") (name "Net-(U1-BYPASS)") (class "Default")
      (node (ref "C9") (pin "2") (pinfunction "2_2") (pintype "passive"))
      (node (ref "U1") (pin "4") (pinfunction "BYPASS_4") (pintype "passive"))
    )
    (net (code "40") (name "Net-(U1-VOUT)") (class "Default")
      (node (ref "C12") (pin "2") (pinfunction "2_2") (pintype "passive"))
      (node (ref "C13") (pin "2") (pinfunction "2_2") (pintype "passive"))
      (node (ref "U1") (pin "5") (pinfunction "VOUT_5") (pintype "passive"))
    )
    (net (code "41") (name "Net-(U2-BOOT0)") (class "Default")
      (node (ref "R6") (pin "1") (pinfunction "1_1") (pintype "passive"))
      (node (ref "U2") (pin "44") (pinfunction "BOOT0_44") (pintype "bidirectional"))
    )
    (net (code "42") (name "Net-(U2-NRST)") (class "Default")
      (node (ref "C6") (pin "2") (pinfunction "2_2") (pintype "passive"))
      (node (ref "R14") (pin "1") (pinfunction "1_1") (pintype "passive"))
      (node (ref "U2") (pin "7") (pinfunction "NRST_7") (pintype "input"))
    )
    (net (code "43") (name "Net-(U2-OSC_OUT)") (class "Default")
      (node (ref "C3") (pin "1") (pinfunction "1_1") (pintype "passive"))
      (node (ref "C8") (pin "1") (pinfunction "1_1") (pintype "passive"))
      (node (ref "U2") (pin "6") (pinfunction "OSC_OUT_6") (pintype "output"))
      (node (ref "X1") (pin "1") (pinfunction "1_1") (pintype "passive"))
      (node (ref "X1") (pin "2") (pinfunction "2_2") (pintype "passive"))
    )
    (net (code "44") (name "Net-(U2-PA0-WKUP)") (class "Default")
      (node (ref "R23") (pin "2") (pinfunction "2_2") (pintype "passive"))
      (node (ref "R27") (pin "2") (pinfunction "2_2") (pintype "passive"))
      (node (ref "U2") (pin "10") (pinfunction "PA0-WKUP_10") (pintype "bidirectional"))
    )
    (net (code "45") (name "Net-(U2-PA8)") (class "Default")
      (node (ref "R25") (pin "1") (pinfunction "1_1") (pintype "passive"))
      (node (ref "U2") (pin "29") (pinfunction "PA8_29") (pintype "bidirectional"))
    )
    (net (code "46") (name "Net-(U2-PB3)") (class "Default")
      (node (ref "JP1") (pin "2") (pinfunction "2_2") (pintype "passive"))
      (node (ref "R4") (pin "1") (pinfunction "1_1") (pintype "passive"))
      (node (ref "R7") (pin "2") (pinfunction "2_2") (pintype "passive"))
      (node (ref "U2") (pin "39") (pinfunction "PB3_39") (pintype "bidirectional"))
    )
    (net (code "47") (name "Net-(U2-PB10)") (class "Default")
      (node (ref "JP4") (pin "2") (pinfunction "2_2") (pintype "passive"))
      (node (ref "R26") (pin "1") (pinfunction "1_1") (pintype "passive"))
      (node (ref "U2") (pin "21") (pinfunction "PB10_21") (pintype "bidirectional"))
    )
    (net (code "48") (name "Net-(U2-PB12)") (class "Default")
      (node (ref "R24") (pin "1") (pinfunction "1_1") (pintype "passive"))
      (node (ref "U2") (pin "25") (pinfunction "PB12_25") (pintype "bidirectional"))
    )
    (net (code "49") (name "Net-(U2-PB14)") (class "Default")
      (node (ref "R24") (pin "2") (pinfunction "2_2") (pintype "passive"))
      (node (ref "U2") (pin "27") (pinfunction "PB14_27") (pintype "bidirectional"))
    )
    (net (code "50") (name "Net-(U2-PC13-TAMPER-RTC)") (class "Default")
      (node (ref "R3") (pin "2") (pinfunction "2_2") (pintype "passive"))
      (node (ref "U2") (pin "2") (pinfunction "PC13-TAMPER-RTC_2") (pintype "bidirectional"))
    )
    (net (code "51") (name "Net-(U2-PC14-OSC32_IN)") (class "Default")
      (node (ref "R2") (pin "2") (pinfunction "2_2") (pintype "passive"))
      (node (ref "U2") (pin "3") (pinfunction "PC14-OSC32_IN_3") (pintype "bidirectional"))
    )
    (net (code "52") (name "U5V") (class "Default")
      (node (ref "CN1") (pin "1") (pinfunction "VBUS_1") (pintype "passive"))
      (node (ref "R12") (pin "2") (pinfunction "2_2") (pintype "passive"))
    )
    (net (code "53") (name "unconnected-(R9-Pad2)") (class "Default")
      (node (ref "R9") (pin "2") (pinfunction "2_2") (pintype "passive"))
    )
    (net (code "54") (name "unconnected-(R11-Pad1)") (class "Default")
      (node (ref "R11") (pin "1") (pinfunction "1_1") (pintype "passive"))
    )
    (net (code "55") (name "unconnected-(R13-Pad2)") (class "Default")
      (node (ref "R13") (pin "2") (pinfunction "2_2") (pintype "passive"))
    )
    (net (code "56") (name "unconnected-(R17-Pad1)") (class "Default")
      (node (ref "R17") (pin "1") (pinfunction "1_1") (pintype "passive"))
    )
    (net (code "57") (name "unconnected-(R18-Pad1)") (class "Default")
      (node (ref "R18") (pin "1") (pinfunction "1_1") (pintype "passive"))
    )
    (net (code "58") (name "unconnected-(R22-Pad2)") (class "Default")
      (node (ref "R22") (pin "2") (pinfunction "2_2") (pintype "passive"))
    )
    (net (code "59") (name "unconnected-(SB6-N.O._2-Pad2)") (class "Default")
      (node (ref "SB6") (pin "2") (pinfunction "N.O._2_2") (pintype "passive"))
    )
    (net (code "60") (name "unconnected-(SB10-N.O._2-Pad2)") (class "Default")
      (node (ref "SB10") (pin "2") (pinfunction "N.O._2_2") (pintype "passive"))
    )
    (net (code "61") (name "unconnected-(SB11-N.O._1-Pad1)") (class "Default")
      (node (ref "SB11") (pin "1") (pinfunction "N.O._1_1") (pintype "passive"))
    )
    (net (code "62") (name "unconnected-(SB11-N.O._2-Pad2)") (class "Default")
      (node (ref "SB11") (pin "2") (pinfunction "N.O._2_2") (pintype "passive"))
    )
    (net (code "63") (name "unconnected-(SB12-N.O._1-Pad1)") (class "Default")
      (node (ref "SB12") (pin "1") (pinfunction "N.O._1_1") (pintype "passive"))
    )
    (net (code "64") (name "unconnected-(SB15-N.O._1-Pad1)") (class "Default")
      (node (ref "SB15") (pin "1") (pinfunction "N.O._1_1") (pintype "passive"))
    )
    (net (code "65") (name "unconnected-(U2-OSC_IN-Pad5)") (class "Default")
      (node (ref "U2") (pin "5") (pinfunction "OSC_IN_5") (pintype "input"))
    )
    (net (code "66") (name "unconnected-(U2-PA1-Pad11)") (class "Default")
      (node (ref "U2") (pin "11") (pinfunction "PA1_11") (pintype "bidirectional"))
    )
    (net (code "67") (name "unconnected-(U2-PA4-Pad14)") (class "Default")
      (node (ref "U2") (pin "14") (pinfunction "PA4_14") (pintype "bidirectional"))
    )
    (net (code "68") (name "unconnected-(U2-PA5-Pad15)") (class "Default")
      (node (ref "U2") (pin "15") (pinfunction "PA5_15") (pintype "bidirectional"))
    )
    (net (code "69") (name "unconnected-(U2-PA6-Pad16)") (class "Default")
      (node (ref "U2") (pin "16") (pinfunction "PA6_16") (pintype "bidirectional"))
    )
    (net (code "70") (name "unconnected-(U2-PA7-Pad17)") (class "Default")
      (node (ref "U2") (pin "17") (pinfunction "PA7_17") (pintype "bidirectional"))
    )
    (net (code "71") (name "unconnected-(U2-PA9-Pad30)") (class "Default")
      (node (ref "U2") (pin "30") (pinfunction "PA9_30") (pintype "bidirectional"))
    )
    (net (code "72") (name "unconnected-(U2-PA10-Pad31)") (class "Default")
      (node (ref "U2") (pin "31") (pinfunction "PA10_31") (pintype "bidirectional"))
    )
    (net (code "73") (name "unconnected-(U2-PA11-Pad32)") (class "Default")
      (node (ref "U2") (pin "32") (pinfunction "PA11_32") (pintype "bidirectional"))
    )
    (net (code "74") (name "unconnected-(U2-PA12-Pad33)") (class "Default")
      (node (ref "U2") (pin "33") (pinfunction "PA12_33") (pintype "bidirectional"))
    )
    (net (code "75") (name "unconnected-(U2-PA13-Pad34)") (class "Default")
      (node (ref "U2") (pin "34") (pinfunction "PA13_34") (pintype "bidirectional"))
    )
    (net (code "76") (name "unconnected-(U2-PA14-Pad37)") (class "Default")
      (node (ref "U2") (pin "37") (pinfunction "PA14_37") (pintype "bidirectional"))
    )
    (net (code "77") (name "unconnected-(U2-PA15-Pad38)") (class "Default")
      (node (ref "U2") (pin "38") (pinfunction "PA15_38") (pintype "bidirectional"))
    )
    (net (code "78") (name "unconnected-(U2-PB0-Pad18)") (class "Default")
      (node (ref "U2") (pin "18") (pinfunction "PB0_18") (pintype "bidirectional"))
    )
    (net (code "79") (name "unconnected-(U2-PB1-Pad19)") (class "Default")
      (node (ref "U2") (pin "19") (pinfunction "PB1_19") (pintype "input"))
    )
    (net (code "80") (name "unconnected-(U2-PB4-Pad40)") (class "Default")
      (node (ref "U2") (pin "40") (pinfunction "PB4_40") (pintype "bidirectional"))
    )
    (net (code "81") (name "unconnected-(U2-PB5-Pad41)") (class "Default")
      (node (ref "U2") (pin "41") (pinfunction "PB5_41") (pintype "bidirectional"))
    )
    (net (code "82") (name "unconnected-(U2-PB6-Pad42)") (class "Default")
      (node (ref "U2") (pin "42") (pinfunction "PB6_42") (pintype "bidirectional"))
    )
    (net (code "83") (name "unconnected-(U2-PB7-Pad43)") (class "Default")
      (node (ref "U2") (pin "43") (pinfunction "PB7_43") (pintype "bidirectional"))
    )
    (net (code "84") (name "unconnected-(U2-PB8-Pad45)") (class "Default")
      (node (ref "U2") (pin "45") (pinfunction "PB8_45") (pintype "bidirectional"))
    )
    (net (code "85") (name "unconnected-(U2-PB9-Pad46)") (class "Default")
      (node (ref "U2") (pin "46") (pinfunction "PB9_46") (pintype "bidirectional"))
    )
    (net (code "86") (name "unconnected-(U2-PB11-Pad22)") (class "Default")
      (node (ref "U2") (pin "22") (pinfunction "PB11_22") (pintype "bidirectional"))
    )
    (net (code "87") (name "unconnected-(U2-PB13-Pad26)") (class "Default")
      (node (ref "U2") (pin "26") (pinfunction "PB13_26") (pintype "bidirectional"))
    )
    (net (code "88") (name "unconnected-(U2-PC15-OSC32_OUT-Pad4)") (class "Default")
      (node (ref "U2") (pin "4") (pinfunction "PC15-OSC32_OUT_4") (pintype "bidirectional"))
    )
  )
)
